# Input.net
KiCad netlist of a schematic drawn in Altium Designer
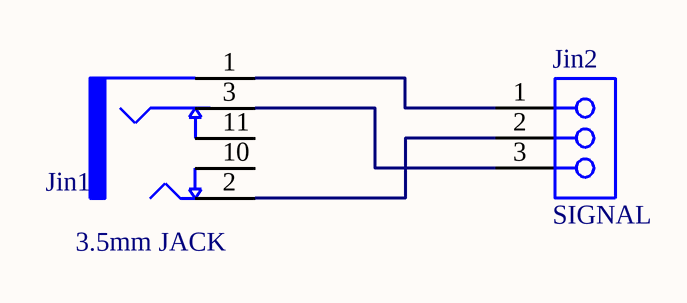
[diagram p0: Input.SchDoc]

(export (version "E")
  (design (tool "Eeschema 10.0.6"))
  (components
    (comp (ref "Jin1")
      (value "3.5mm JACK")
      (footprint "SWITCHCRAFT_35RAPC4BHN2")
      (description "Conn 3.5MM Stereo Jack F 5 POS Solder RA Thru-Hole 5 Terminal 1 Port")
      (fields (field (name "MP") "35RAPC4BHN2") (field (name "MF") "{'manufacturer': u'Switchcraft Inc.'}"))
      (libsource (lib "SnapEDA_Library") (part "35RAPC4BHN2"))
    )
    (comp (ref "Jin2")
      (value "SIGNAL")
      (footprint "SMTC-SLW-103-01-X-S")
      (fields (field (name "MANUFACTURER") "Samtec") (field (name "PARTNUMBER") "SLW-103-01-G-S"))
      (libsource (lib "Altium Content Vault") (part "SMTC-SLW-103-01-X-S"))
    )
  )
  (nets
    (net (code "1") (name "Net-(Jin1-Pad1)") (class "Default")
      (node (ref "Jin1") (pin "1") (pinfunction "1_1") (pintype "passive"))
      (node (ref "Jin2") (pin "1") (pinfunction "1_1") (pintype "passive"))
    )
    (net (code "2") (name "Net-(Jin1-Pad2)") (class "Default")
      (node (ref "Jin1") (pin "2") (pinfunction "2_2") (pintype "passive"))
      (node (ref "Jin2") (pin "2") (pinfunction "2_2") (pintype "passive"))
    )
    (net (code "3") (name "Net-(Jin1-Pad3)") (class "Default")
      (node (ref "Jin1") (pin "3") (pinfunction "3_3") (pintype "passive"))
      (node (ref "Jin2") (pin "3") (pinfunction "3_3") (pintype "passive"))
    )
    (net (code "4") (name "unconnected-(Jin1-Pad10)") (class "Default")
      (node (ref "Jin1") (pin "10") (pinfunction "10_10") (pintype "passive"))
    )
    (net (code "5") (name "unconnected-(Jin1-Pad11)") (class "Default")
      (node (ref "Jin1") (pin "11") (pinfunction "11_11") (pintype "passive"))
    )
  )
)
